# D5035-01.net
KiCad netlist of a schematic drawn in Altium Designer
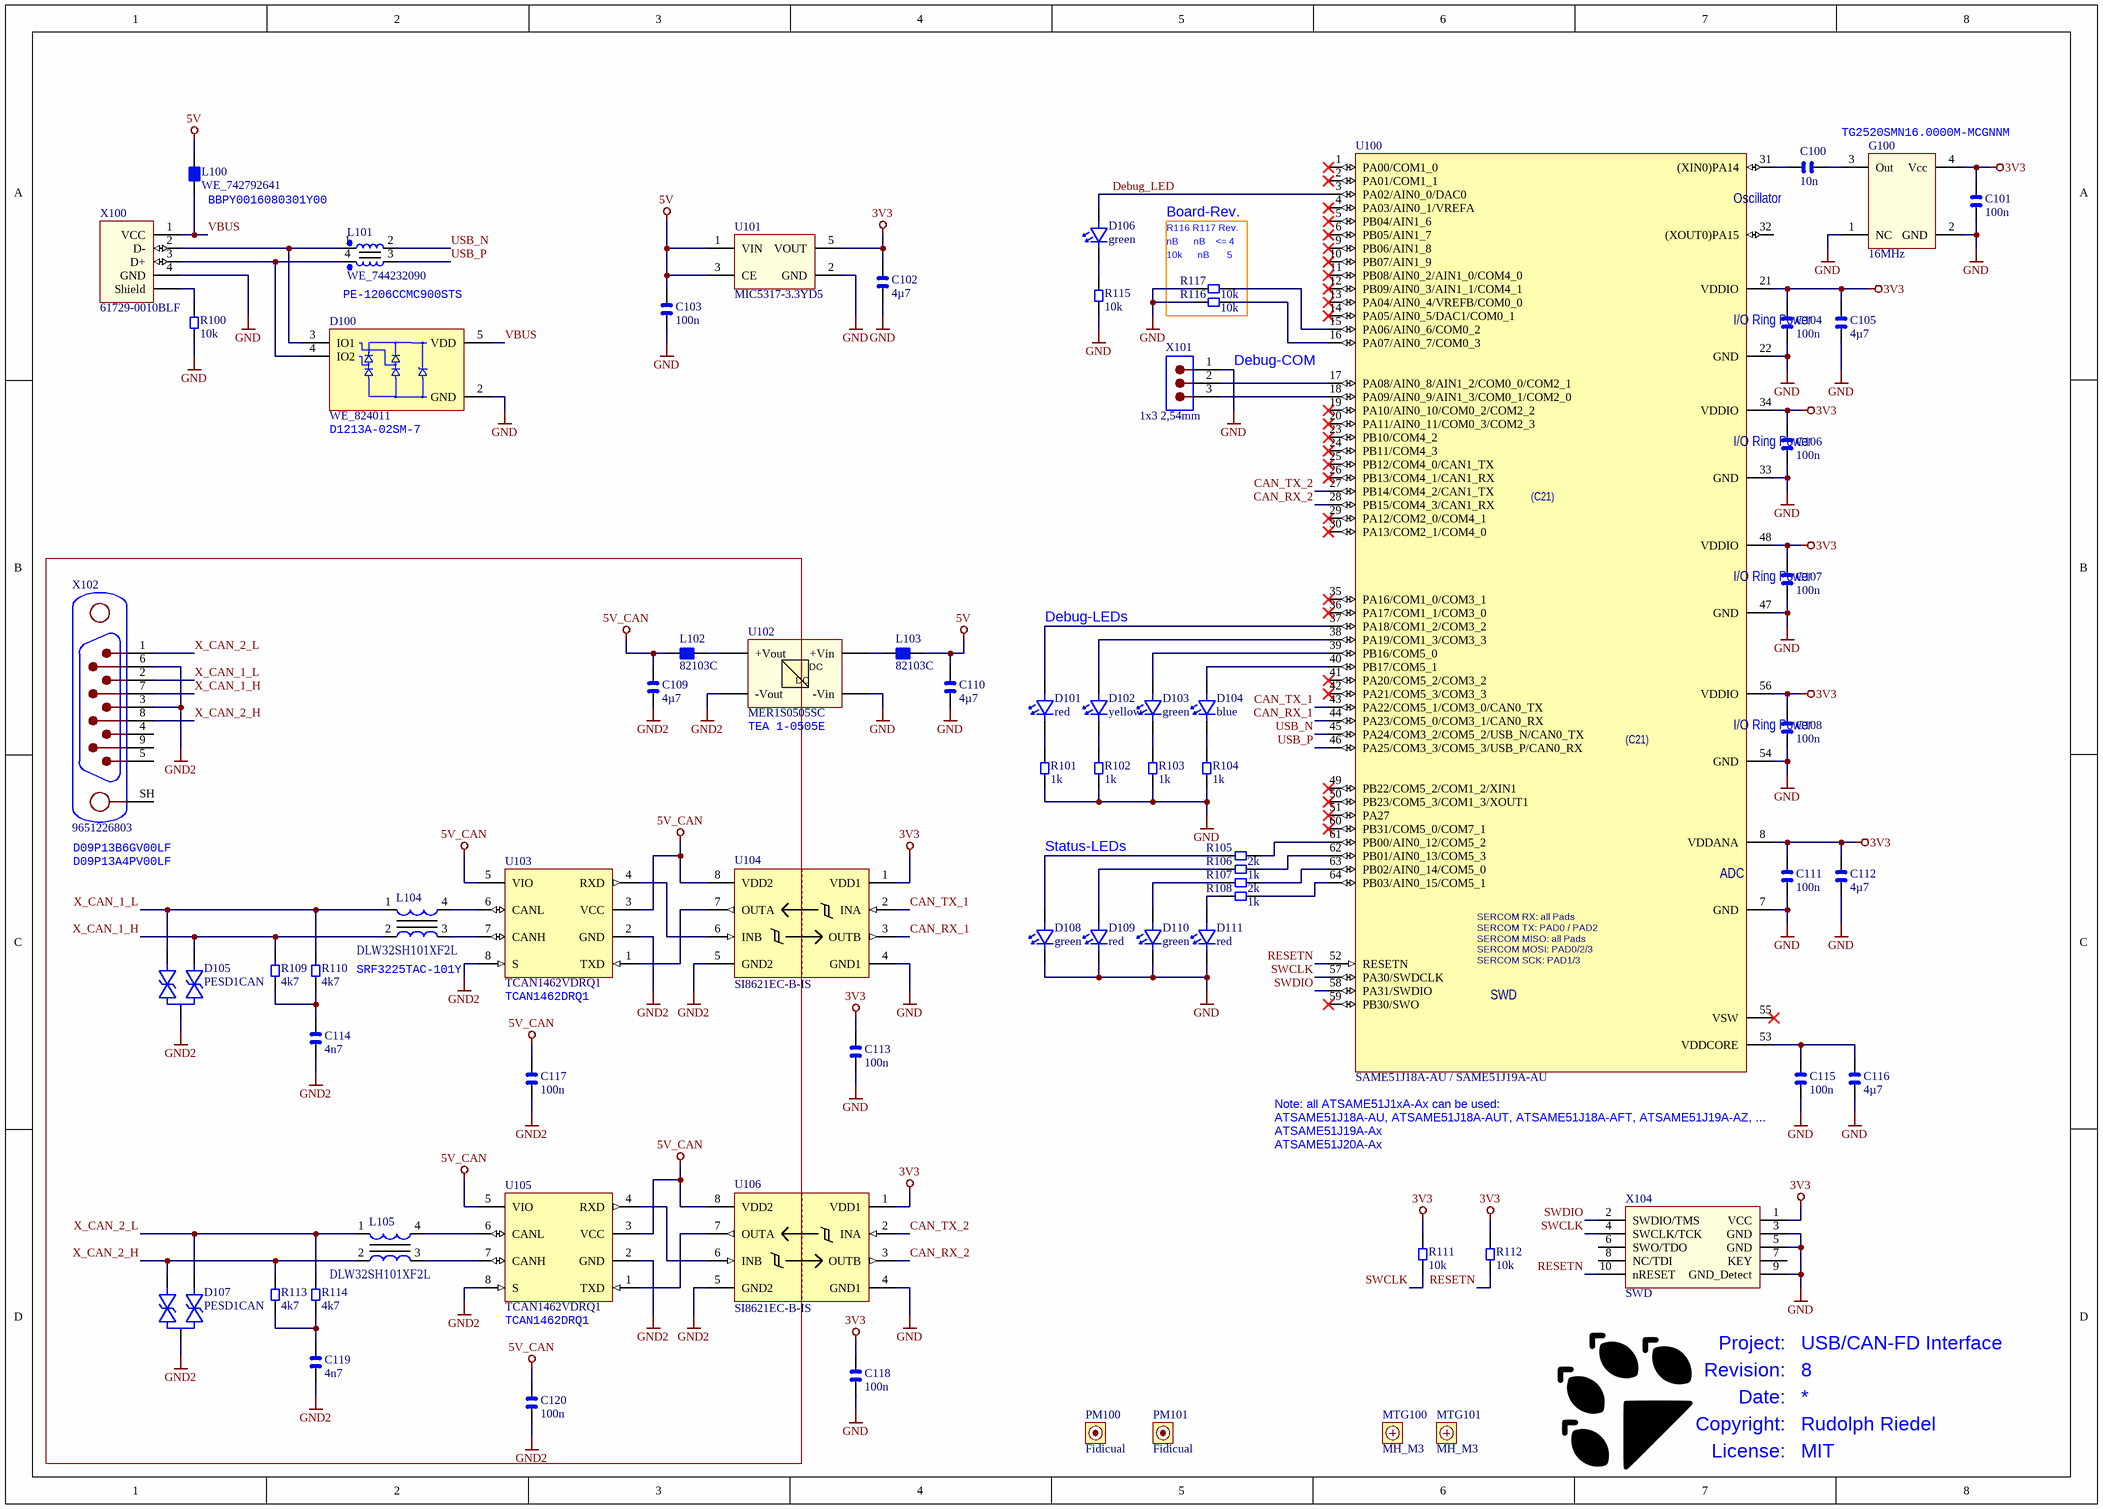
[diagram p0: D5035-01.SchDoc]

(export (version "E")
  (design (tool "Eeschema 10.0.6"))
  (components
    (comp (ref "C100")
      (value "10n")
      (footprint "CAPC1608X09L")
      (description "0603 Chip Capacitor")
      (fields (field (name "PART NUMBER") "CAPC_0603") (field (name "EDITOR") "rriedel"))
      (libsource (lib "HW-Labor_GF") (part "CAP_2_V2"))
    )
    (comp (ref "C101")
      (value "100n")
      (footprint "CAPC1608X09L")
      (description "0603 Chip Capacitor")
      (fields (field (name "PART NUMBER") "CAPC_0603") (field (name "EDITOR") "rriedel"))
      (libsource (lib "HW-Labor_GF") (part "CAP_2_V2"))
    )
    (comp (ref "C102")
      (value "4µ7")
      (footprint "CAPC2012X14L")
      (description "0805 Chip Capacitor")
      (fields (field (name "PART NUMBER") "CAPC_0805") (field (name "EDITOR") "rriedel"))
      (libsource (lib "HW-Labor_GF") (part "CAP_2_V2"))
    )
    (comp (ref "C103")
      (value "100n")
      (footprint "CAPC1608X09L")
      (description "0603 Chip Capacitor")
      (fields (field (name "PART NUMBER") "CAPC_0603") (field (name "EDITOR") "rriedel"))
      (libsource (lib "HW-Labor_GF") (part "CAP_2_V2"))
    )
    (comp (ref "C104")
      (value "100n")
      (footprint "CAPC1608X09L")
      (description "0603 Chip Capacitor")
      (fields (field (name "PART NUMBER") "CAPC_0603") (field (name "EDITOR") "rriedel"))
      (libsource (lib "HW-Labor_GF") (part "CAP_2_V2"))
    )
    (comp (ref "C105")
      (value "4µ7")
      (footprint "CAPC2012X14L")
      (description "0805 Chip Capacitor")
      (fields (field (name "PART NUMBER") "CAPC_0805") (field (name "EDITOR") "rriedel"))
      (libsource (lib "HW-Labor_GF") (part "CAP_2_V2"))
    )
    (comp (ref "C106")
      (value "100n")
      (footprint "CAPC1608X09L")
      (description "0603 Chip Capacitor")
      (fields (field (name "PART NUMBER") "CAPC_0603") (field (name "EDITOR") "rriedel"))
      (libsource (lib "HW-Labor_GF") (part "CAP_2_V2"))
    )
    (comp (ref "C107")
      (value "100n")
      (footprint "CAPC1608X09L")
      (description "0603 Chip Capacitor")
      (fields (field (name "PART NUMBER") "CAPC_0603") (field (name "EDITOR") "rriedel"))
      (libsource (lib "HW-Labor_GF") (part "CAP_2_V2"))
    )
    (comp (ref "C108")
      (value "100n")
      (footprint "CAPC1608X09L")
      (description "0603 Chip Capacitor")
      (fields (field (name "PART NUMBER") "CAPC_0603") (field (name "EDITOR") "rriedel"))
      (libsource (lib "HW-Labor_GF") (part "CAP_2_V2"))
    )
    (comp (ref "C109")
      (value "4µ7")
      (footprint "CAPC2012X14L")
      (description "0805 Chip Capacitor")
      (fields (field (name "PART NUMBER") "CAPC_0805") (field (name "EDITOR") "rriedel"))
      (libsource (lib "HW-Labor_GF") (part "CAP_2_V2"))
    )
    (comp (ref "C110")
      (value "4µ7")
      (footprint "CAPC2012X14L")
      (description "0805 Chip Capacitor")
      (fields (field (name "PART NUMBER") "CAPC_0805") (field (name "EDITOR") "rriedel"))
      (libsource (lib "HW-Labor_GF") (part "CAP_2_V2"))
    )
    (comp (ref "C111")
      (value "100n")
      (footprint "CAPC1608X09L")
      (description "0603 Chip Capacitor")
      (fields (field (name "PART NUMBER") "CAPC_0603") (field (name "EDITOR") "rriedel"))
      (libsource (lib "HW-Labor_GF") (part "CAP_2_V2"))
    )
    (comp (ref "C112")
      (value "4µ7")
      (footprint "CAPC2012X14L")
      (description "0805 Chip Capacitor")
      (fields (field (name "PART NUMBER") "CAPC_0805") (field (name "EDITOR") "rriedel"))
      (libsource (lib "HW-Labor_GF") (part "CAP_2_V2"))
    )
    (comp (ref "C113")
      (value "100n")
      (footprint "CAPC1608X09L")
      (description "0603 Chip Capacitor")
      (fields (field (name "PART NUMBER") "CAPC_0603") (field (name "EDITOR") "rriedel"))
      (libsource (lib "HW-Labor_GF") (part "CAP_2_V2"))
    )
    (comp (ref "C114")
      (value "4n7")
      (footprint "CAPC2012X14L")
      (description "0805 Chip Capacitor")
      (fields (field (name "PART NUMBER") "CAPC_0805") (field (name "EDITOR") "rriedel"))
      (libsource (lib "HW-Labor_GF") (part "CAP_2_V2"))
    )
    (comp (ref "C115")
      (value "100n")
      (footprint "CAPC1608X09L")
      (description "0603 Chip Capacitor")
      (fields (field (name "PART NUMBER") "CAPC_0603") (field (name "EDITOR") "rriedel"))
      (libsource (lib "HW-Labor_GF") (part "CAP_2_V2"))
    )
    (comp (ref "C116")
      (value "4µ7")
      (footprint "CAPC2012X14L")
      (description "0805 Chip Capacitor")
      (fields (field (name "PART NUMBER") "CAPC_0805") (field (name "EDITOR") "rriedel"))
      (libsource (lib "HW-Labor_GF") (part "CAP_2_V2"))
    )
    (comp (ref "C117")
      (value "100n")
      (footprint "CAPC1608X09L")
      (description "0603 Chip Capacitor")
      (fields (field (name "PART NUMBER") "CAPC_0603") (field (name "EDITOR") "rriedel"))
      (libsource (lib "HW-Labor_GF") (part "CAP_2_V2"))
    )
    (comp (ref "C118")
      (value "100n")
      (footprint "CAPC1608X09L")
      (description "0603 Chip Capacitor")
      (fields (field (name "PART NUMBER") "CAPC_0603") (field (name "EDITOR") "rriedel"))
      (libsource (lib "HW-Labor_GF") (part "CAP_2_V2"))
    )
    (comp (ref "C119")
      (value "4n7")
      (footprint "CAPC2012X14L")
      (description "0805 Chip Capacitor")
      (fields (field (name "PART NUMBER") "CAPC_0805") (field (name "EDITOR") "rriedel"))
      (libsource (lib "HW-Labor_GF") (part "CAP_2_V2"))
    )
    (comp (ref "C120")
      (value "100n")
      (footprint "CAPC1608X09L")
      (description "0603 Chip Capacitor")
      (fields (field (name "PART NUMBER") "CAPC_0603") (field (name "EDITOR") "rriedel"))
      (libsource (lib "HW-Labor_GF") (part "CAP_2_V2"))
    )
    (comp (ref "D100")
      (value "WE_824011")
      (footprint "SOT95P280X110-5N")
      (description "TVS Diode Array WE-TVS")
      (fields
        (field (name "MANUFACTURER") "Wuerth")
        (field (name "DISTRIBUTOR_1_PART_NUMBER") "732-4465-1-ND")
        (field (name "EDITOR") "rriedel")
      )
      (libsource (lib "HW-Labor_GF") (part "WE-824011"))
    )
    (comp (ref "D101")
      (value "red")
      (footprint "DIOC1608X06N_LED")
      (description "LED, 0603")
      (fields (field (name "PART NUMBER") "LED_0603") (field (name "EDITOR") "rriedel"))
      (libsource (lib "HW-Labor_GF") (part "LED_generic"))
    )
    (comp (ref "D102")
      (value "yellow")
      (footprint "DIOC1608X06N_LED")
      (description "LED, 0603")
      (fields (field (name "PART NUMBER") "LED_0603") (field (name "EDITOR") "rriedel"))
      (libsource (lib "HW-Labor_GF") (part "LED_generic"))
    )
    (comp (ref "D103")
      (value "green")
      (footprint "DIOC1608X06N_LED")
      (description "LED, 0603")
      (fields (field (name "PART NUMBER") "LED_0603") (field (name "EDITOR") "rriedel"))
      (libsource (lib "HW-Labor_GF") (part "LED_generic"))
    )
    (comp (ref "D104")
      (value "blue")
      (footprint "DIOC1608X06N_LED")
      (description "LED, 0603")
      (fields (field (name "PART NUMBER") "LED_0603") (field (name "EDITOR") "rriedel"))
      (libsource (lib "HW-Labor_GF") (part "LED_generic"))
    )
    (comp (ref "D105")
      (value "PESD1CAN")
      (footprint "SOT95P280X110-3N")
      (description "CAN bus ESD protection diode")
      (fields
        (field (name "MANUFACTURER") "Nexperia")
        (field (name "DISTRIBUTOR_1_PART_NUMBER") "1727-3817-1-ND")
        (field (name "EDITOR") "rriedel")
      )
      (libsource (lib "HW-Labor_GF") (part "PESD1CAN"))
    )
    (comp (ref "D106")
      (value "green")
      (footprint "DIOC1608X06N_LED")
      (description "LED, 0603")
      (fields (field (name "PART NUMBER") "LED_0603") (field (name "EDITOR") "rriedel"))
      (libsource (lib "HW-Labor_GF") (part "LED_generic"))
    )
    (comp (ref "D107")
      (value "PESD1CAN")
      (footprint "SOT95P280X110-3N")
      (description "CAN bus ESD protection diode")
      (fields
        (field (name "MANUFACTURER") "Nexperia")
        (field (name "DISTRIBUTOR_1_PART_NUMBER") "1727-3817-1-ND")
        (field (name "EDITOR") "rriedel")
      )
      (libsource (lib "HW-Labor_GF") (part "PESD1CAN"))
    )
    (comp (ref "D108")
      (value "green")
      (footprint "DIOC1608X06N_LED")
      (description "LED, 0603")
      (fields (field (name "PART NUMBER") "LED_0603") (field (name "EDITOR") "rriedel"))
      (libsource (lib "HW-Labor_GF") (part "LED_generic"))
    )
    (comp (ref "D109")
      (value "red")
      (footprint "DIOC1608X06N_LED")
      (description "LED, 0603")
      (fields (field (name "PART NUMBER") "LED_0603") (field (name "EDITOR") "rriedel"))
      (libsource (lib "HW-Labor_GF") (part "LED_generic"))
    )
    (comp (ref "D110")
      (value "green")
      (footprint "DIOC1608X06N_LED")
      (description "LED, 0603")
      (fields (field (name "PART NUMBER") "LED_0603") (field (name "EDITOR") "rriedel"))
      (libsource (lib "HW-Labor_GF") (part "LED_generic"))
    )
    (comp (ref "D111")
      (value "red")
      (footprint "DIOC1608X06N_LED")
      (description "LED, 0603")
      (fields (field (name "PART NUMBER") "LED_0603") (field (name "EDITOR") "rriedel"))
      (libsource (lib "HW-Labor_GF") (part "LED_generic"))
    )
    (comp (ref "G100")
      (value "16MHz")
      (footprint "TG2520")
      (description "16MHz Oscillator, +/- 0.5ppm")
      (fields
        (field (name "PART NUMBER") "TG2520SMN16.0000M-MCGNNM")
        (field (name "MANUFACTURER") "Epson")
        (field (name "EDITOR") "rriedel")
      )
      (libsource (lib "HW-Labor_GF") (part "TG2520"))
    )
    (comp (ref "L100")
      (value "WE_742792641")
      (footprint "INDC1608X06L")
      (description "SMT EMI suppression ferrite bead WE-CBF")
      (fields
        (field (name "MANUFACTURER") "Wuerth")
        (field (name "DISTRIBUTOR_1_PART_NUMBER") "732-1592-1-ND")
        (field (name "EDITOR") "rriedel")
      )
      (libsource (lib "HW-Labor_GF") (part "IND_2_V1"))
    )
    (comp (ref "L101")
      (value "WE_744232090")
      (footprint "WE_744232090")
      (description "SMD common mode noise suppressor WE-CNSW")
      (fields
        (field (name "MANUFACTURER") "Wuerth")
        (field (name "DISTRIBUTOR_1_PART_NUMBER") "732-1469-1-ND")
        (field (name "EDITOR") "rriedel")
      )
      (libsource (lib "HW-Labor_GF") (part "WE_744232090"))
    )
    (comp (ref "L102")
      (value "82103C")
      (footprint "Murata_8200C")
      (description "10µH, 0,5A, 400mR")
      (fields
        (field (name "MANUFACTURER") "Murata")
        (field (name "DISTRIBUTOR_1_PART_NUMBER") "811-2473-1-ND")
        (field (name "EDITOR") "rriedel")
      )
      (libsource (lib "HW-Labor_GF") (part "IND_2_V1"))
    )
    (comp (ref "L103")
      (value "82103C")
      (footprint "Murata_8200C")
      (description "10µH, 0,5A, 400mR")
      (fields
        (field (name "MANUFACTURER") "Murata")
        (field (name "DISTRIBUTOR_1_PART_NUMBER") "811-2473-1-ND")
        (field (name "EDITOR") "rriedel")
      )
      (libsource (lib "HW-Labor_GF") (part "IND_2_V1"))
    )
    (comp (ref "L104")
      (value "DLW32SH101XF2L‎")
      (footprint "ACT1210")
      (description "Common Mode Filter,  -50°C ... +150°C, AEC-Q200")
      (fields
        (field (name "PART NUMBER") "ACT1210-101-2P-TL00")
        (field (name "MANUFACTURER") "TDK")
        (field (name "EDITOR") "rriedel")
      )
      (libsource (lib "HW-Labor_GF") (part "CAN_DROSSEL"))
    )
    (comp (ref "L105")
      (value "DLW32SH101XF2L‎")
      (footprint "ACT1210")
      (description "Common Mode Filter,  -50°C ... +150°C, AEC-Q200")
      (fields
        (field (name "PART NUMBER") "ACT1210-101-2P-TL00")
        (field (name "MANUFACTURER") "TDK")
        (field (name "EDITOR") "rriedel")
      )
      (libsource (lib "HW-Labor_GF") (part "CAN_DROSSEL"))
    )
    (comp (ref "MTG100")
      (value "MH_M3")
      (footprint "HOLE_3_2MM")
      (description "Mounting-Hole for M3 screws")
      (fields (field (name "EDITOR") "rriedel"))
      (libsource (lib "HW-Labor_GF") (part "MTG_V1"))
    )
    (comp (ref "MTG101")
      (value "MH_M3")
      (footprint "HOLE_3_2MM")
      (description "Mounting-Hole for M3 screws")
      (fields (field (name "EDITOR") "rriedel"))
      (libsource (lib "HW-Labor_GF") (part "MTG_V1"))
    )
    (comp (ref "PM100")
      (value "Fidicual")
      (footprint "PM100")
      (fields (field (name "PART NUMBER") "PM100") (field (name "EDITOR") "rriedel"))
      (libsource (lib "HW-Labor_GF") (part "PM100"))
    )
    (comp (ref "PM101")
      (value "Fidicual")
      (footprint "PM100")
      (fields (field (name "PART NUMBER") "PM100") (field (name "EDITOR") "rriedel"))
      (libsource (lib "HW-Labor_GF") (part "PM100"))
    )
    (comp (ref "R100")
      (value "10k")
      (footprint "RESC1608X06L")
      (description "0603 Chip Resistor")
      (fields (field (name "PART NUMBER") "RESC_0603") (field (name "EDITOR") "rriedel"))
      (libsource (lib "HW-Labor_GF") (part "RES_2_V2"))
    )
    (comp (ref "R101")
      (value "1k")
      (footprint "RESC1608X06L")
      (description "0603 Chip Resistor")
      (fields (field (name "PART NUMBER") "RESC_0603") (field (name "EDITOR") "rriedel"))
      (libsource (lib "HW-Labor_GF") (part "RES_2_V2"))
    )
    (comp (ref "R102")
      (value "1k")
      (footprint "RESC1608X06L")
      (description "0603 Chip Resistor")
      (fields (field (name "PART NUMBER") "RESC_0603") (field (name "EDITOR") "rriedel"))
      (libsource (lib "HW-Labor_GF") (part "RES_2_V2"))
    )
    (comp (ref "R103")
      (value "1k")
      (footprint "RESC1608X06L")
      (description "0603 Chip Resistor")
      (fields (field (name "PART NUMBER") "RESC_0603") (field (name "EDITOR") "rriedel"))
      (libsource (lib "HW-Labor_GF") (part "RES_2_V2"))
    )
    (comp (ref "R104")
      (value "1k")
      (footprint "RESC1608X06L")
      (description "0603 Chip Resistor")
      (fields (field (name "PART NUMBER") "RESC_0603") (field (name "EDITOR") "rriedel"))
      (libsource (lib "HW-Labor_GF") (part "RES_2_V2"))
    )
    (comp (ref "R105")
      (value "2k")
      (footprint "RESC1608X06L")
      (description "0603 Chip Resistor")
      (fields (field (name "PART NUMBER") "RESC_0603") (field (name "EDITOR") "rriedel"))
      (libsource (lib "HW-Labor_GF") (part "RES_2_V2"))
    )
    (comp (ref "R106")
      (value "1k")
      (footprint "RESC1608X06L")
      (description "0603 Chip Resistor")
      (fields (field (name "PART NUMBER") "RESC_0603") (field (name "EDITOR") "rriedel"))
      (libsource (lib "HW-Labor_GF") (part "RES_2_V2"))
    )
    (comp (ref "R107")
      (value "2k")
      (footprint "RESC1608X06L")
      (description "0603 Chip Resistor")
      (fields (field (name "PART NUMBER") "RESC_0603") (field (name "EDITOR") "rriedel"))
      (libsource (lib "HW-Labor_GF") (part "RES_2_V2"))
    )
    (comp (ref "R108")
      (value "1k")
      (footprint "RESC1608X06L")
      (description "0603 Chip Resistor")
      (fields (field (name "PART NUMBER") "RESC_0603") (field (name "EDITOR") "rriedel"))
      (libsource (lib "HW-Labor_GF") (part "RES_2_V2"))
    )
    (comp (ref "R109")
      (value "4k7")
      (footprint "RESC2012X06L")
      (description "0805 Chip Resistor")
      (fields (field (name "PART NUMBER") "RESC_0805") (field (name "EDITOR") "rriedel"))
      (libsource (lib "HW-Labor_GF") (part "RES_2_V2"))
    )
    (comp (ref "R110")
      (value "4k7")
      (footprint "RESC2012X06L")
      (description "0805 Chip Resistor")
      (fields (field (name "PART NUMBER") "RESC_0805") (field (name "EDITOR") "rriedel"))
      (libsource (lib "HW-Labor_GF") (part "RES_2_V2"))
    )
    (comp (ref "R111")
      (value "10k")
      (footprint "RESC1608X06L")
      (description "0603 Chip Resistor")
      (fields (field (name "PART NUMBER") "RESC_0603") (field (name "EDITOR") "rriedel"))
      (libsource (lib "HW-Labor_GF") (part "RES_2_V2"))
    )
    (comp (ref "R112")
      (value "10k")
      (footprint "RESC1608X06L")
      (description "0603 Chip Resistor")
      (fields (field (name "PART NUMBER") "RESC_0603") (field (name "EDITOR") "rriedel"))
      (libsource (lib "HW-Labor_GF") (part "RES_2_V2"))
    )
    (comp (ref "R113")
      (value "4k7")
      (footprint "RESC2012X06L")
      (description "0805 Chip Resistor")
      (fields (field (name "PART NUMBER") "RESC_0805") (field (name "EDITOR") "rriedel"))
      (libsource (lib "HW-Labor_GF") (part "RES_2_V2"))
    )
    (comp (ref "R114")
      (value "4k7")
      (footprint "RESC2012X06L")
      (description "0805 Chip Resistor")
      (fields (field (name "PART NUMBER") "RESC_0805") (field (name "EDITOR") "rriedel"))
      (libsource (lib "HW-Labor_GF") (part "RES_2_V2"))
    )
    (comp (ref "R115")
      (value "10k")
      (footprint "RESC1608X06L")
      (description "0603 Chip Resistor")
      (fields (field (name "PART NUMBER") "RESC_0603") (field (name "EDITOR") "rriedel"))
      (libsource (lib "HW-Labor_GF") (part "RES_2_V2"))
    )
    (comp (ref "R116")
      (value "10k")
      (footprint "RESC1608X06L")
      (description "0603 Chip Resistor")
      (fields (field (name "PART NUMBER") "RESC_0603") (field (name "EDITOR") "rriedel"))
      (libsource (lib "HW-Labor_GF") (part "RES_2_V2"))
    )
    (comp (ref "R117")
      (value "10k")
      (footprint "RESC1608X06L")
      (description "0603 Chip Resistor")
      (fields (field (name "PART NUMBER") "RESC_0603") (field (name "EDITOR") "rriedel"))
      (libsource (lib "HW-Labor_GF") (part "RES_2_V2"))
    )
    (comp (ref "U100")
      (value "SAME51J18A-AU / SAME51J19A-AU")
      (footprint "TSQFP50P1200X1200X120-64N")
      (description "32-bit Microcontroller, 120MHz Cortex M4-F, 512k FLASH,  2x CAN-FD, -40…85°C")
      (fields
        (field (name "PART NUMBER") "SAME51J19A-AU")
        (field (name "MANUFACTURER") "Microchip")
        (field (name "EDITOR") "rriedel")
      )
      (libsource (lib "HW-Labor_GF") (part "SAME5xJxxA-AUx"))
    )
    (comp (ref "U101")
      (value "MIC5317-3.3YD5")
      (footprint "SOT95P280X110-5N")
      (description "100 mA LDO,  Vout= 3,3V, -40°C..125°C")
      (fields
        (field (name "PART NUMBER") "MIC5233-3.3")
        (field (name "MANUFACTURER") "Microchip")
        (field (name "EDITOR") "rriedel")
      )
      (libsource (lib "HW-Labor_GF") (part "LDO_SOT23-5"))
    )
    (comp (ref "U102")
      (value "MER1S0505SC")
      (footprint "MER1SxxxxC")
      (description "Isolated 1W Single Output DC-DC Converters 5V/5V 200mA")
      (fields
        (field (name "MANUFACTURER") "Murata")
        (field (name "DISTRIBUTOR_1_PART_NUMBER") "811-2124-5-ND‎")
        (field (name "EDITOR") "rriedel")
      )
      (libsource (lib "HW-Labor_GF") (part "MER1SxxxxC"))
    )
    (comp (ref "U103")
      (value "TCAN1462VDRQ1")
      (footprint "SOIC127P600X175-8N")
      (description "CAN-FD SIC transceiver 8MBit, VIO Pin")
      (fields
        (field (name "MANUFACTURER") "TI")
        (field (name "DISTRIBUTOR_1_PART_NUMBER") "595-TCAN1462VDRQ1")
        (field (name "EDITOR") "rriedel")
      )
      (libsource (lib "HW-Labor_GF") (part "TJA1051T_3"))
    )
    (comp (ref "U104")
      (value "SI8621EC-B-IS")
      (footprint "SOIC127P600X175-8N")
      (description "Dual channel digital isolator, 150Mbit, 3,75kV")
      (fields
        (field (name "MANUFACTURER") "Silicon Labs")
        (field (name "DISTRIBUTOR_1_PART_NUMBER") "336-4776-1-ND")
        (field (name "EDITOR") "rriedel")
      )
      (libsource (lib "HW-Labor_GF") (part "SI8621"))
    )
    (comp (ref "U105")
      (value "TCAN1462VDRQ1")
      (footprint "SOIC127P600X175-8N")
      (description "CAN-FD SIC transceiver 8MBit, VIO Pin")
      (fields
        (field (name "MANUFACTURER") "TI")
        (field (name "DISTRIBUTOR_1_PART_NUMBER") "595-TCAN1462VDRQ1")
        (field (name "EDITOR") "rriedel")
      )
      (libsource (lib "HW-Labor_GF") (part "TJA1051T_3"))
    )
    (comp (ref "U106")
      (value "SI8621EC-B-IS")
      (footprint "SOIC127P600X175-8N")
      (description "Dual channel digital isolator, 150Mbit, 3,75kV")
      (fields
        (field (name "MANUFACTURER") "Silicon Labs")
        (field (name "DISTRIBUTOR_1_PART_NUMBER") "336-4776-1-ND")
        (field (name "EDITOR") "rriedel")
      )
      (libsource (lib "HW-Labor_GF") (part "SI8621"))
    )
    (comp (ref "X100")
      (value "61729-0010BLF")
      (footprint "61729-xxxxxLF")
      (description "USB-B socket, THT")
      (fields
        (field (name "MANUFACTURER") "Amphenol")
        (field (name "DISTRIBUTOR_1_PART_NUMBER") "609-1039-ND")
        (field (name "EDITOR") "rriedel")
      )
      (libsource (lib "HW-Labor_GF") (part "USB"))
    )
    (comp (ref "X101")
      (value "1x3 2,54mm")
      (footprint "PINH_1x03_2_54mm")
      (description "Pin-Header 2,54 mm 3pins")
      (fields (field (name "PART NUMBER") "PINH_1x3_2_54") (field (name "EDITOR") "rriedel"))
      (libsource (lib "HW-Labor_GF") (part "CONM_1x3_V2"))
    )
    (comp (ref "X102")
      (value "9651226803")
      (footprint "09651226803")
      (description "D-Sub, 9 pin, male, right angle")
      (fields
        (field (name "PART NUMBER") "09651226803")
        (field (name "MANUFACTURER") "Harting")
        (field (name "EDITOR") "rriedel")
      )
      (libsource (lib "HW-Labor_GF") (part "D_Sub_9_Male"))
    )
    (comp (ref "X104")
      (value "SWD")
      (footprint "FTSH-105-01-L-DV-K")
      (description "ARM Debug-Header 2x5 1,27 mm")
      (fields (field (name "EDITOR") "rriedel"))
      (libsource (lib "HW-Labor_GF") (part "SWD"))
    )
  )
  (nets
    (net (code "1") (name "/CAN_RX_1") (class "Default")
      (node (ref "U100") (pin "44") (pinfunction "PA23/COM5_0/COM3_1/CAN0_RX_44") (pintype "bidirectional"))
      (node (ref "U104") (pin "3") (pinfunction "OUTB_3") (pintype "output"))
    )
    (net (code "2") (name "/CAN_RX_2") (class "Default")
      (node (ref "U100") (pin "28") (pinfunction "PB15/COM4_3/CAN1_RX_28") (pintype "bidirectional"))
      (node (ref "U106") (pin "3") (pinfunction "OUTB_3") (pintype "output"))
    )
    (net (code "3") (name "/CAN_TX_1") (class "Default")
      (node (ref "U100") (pin "43") (pinfunction "PA22/COM5_1/COM3_0/CAN0_TX_43") (pintype "bidirectional"))
      (node (ref "U104") (pin "2") (pinfunction "INA_2") (pintype "input"))
    )
    (net (code "4") (name "/CAN_TX_2") (class "Default")
      (node (ref "U100") (pin "27") (pinfunction "PB14/COM4_2/CAN1_TX_27") (pintype "bidirectional"))
      (node (ref "U106") (pin "2") (pinfunction "INA_2") (pintype "input"))
    )
    (net (code "5") (name "/Debug_LED") (class "Default")
      (node (ref "D106") (pin "2") (pinfunction "2_2") (pintype "passive"))
      (node (ref "U100") (pin "3") (pinfunction "PA02/AIN0_0/DAC0_3") (pintype "bidirectional"))
    )
    (net (code "6") (name "/RESETN") (class "Default")
      (node (ref "R112") (pin "1") (pinfunction "1_1") (pintype "passive"))
      (node (ref "U100") (pin "52") (pinfunction "RESETN_52") (pintype "input"))
      (node (ref "X104") (pin "10") (pinfunction "nRESET_10") (pintype "passive"))
    )
    (net (code "7") (name "/SWCLK") (class "Default")
      (node (ref "R111") (pin "1") (pinfunction "1_1") (pintype "passive"))
      (node (ref "U100") (pin "57") (pinfunction "PA30/SWDCLK_57") (pintype "bidirectional"))
      (node (ref "X104") (pin "4") (pinfunction "SWCLK/TCK_4") (pintype "passive"))
    )
    (net (code "8") (name "/SWDIO") (class "Default")
      (node (ref "U100") (pin "58") (pinfunction "PA31/SWDIO_58") (pintype "bidirectional"))
      (node (ref "X104") (pin "2") (pinfunction "SWDIO/TMS_2") (pintype "passive"))
    )
    (net (code "9") (name "/USB_N") (class "Default")
      (node (ref "L101") (pin "2") (pinfunction "2_2") (pintype "passive"))
      (node (ref "U100") (pin "45") (pinfunction "PA24/COM3_2/COM5_2/USB_N/CAN0_TX_45") (pintype "bidirectional"))
    )
    (net (code "10") (name "/USB_P") (class "Default")
      (node (ref "L101") (pin "3") (pinfunction "3_3") (pintype "passive"))
      (node (ref "U100") (pin "46") (pinfunction "PA25/COM3_3/COM5_3/USB_P/CAN0_RX_46") (pintype "bidirectional"))
    )
    (net (code "11") (name "/VBUS") (class "Default")
      (node (ref "D100") (pin "5") (pinfunction "VDD_5") (pintype "passive"))
      (node (ref "L100") (pin "1") (pinfunction "1_1") (pintype "passive"))
      (node (ref "X100") (pin "1") (pinfunction "VCC_1") (pintype "power_in"))
    )
    (net (code "12") (name "/X_CAN_1_H") (class "Default")
      (node (ref "D105") (pin "2") (pinfunction "2_2") (pintype "passive"))
      (node (ref "L104") (pin "2") (pintype "passive"))
      (node (ref "R109") (pin "2") (pinfunction "2_2") (pintype "passive"))
      (node (ref "X102") (pin "7") (pinfunction "7_7") (pintype "passive"))
    )
    (net (code "13") (name "/X_CAN_1_L") (class "Default")
      (node (ref "D105") (pin "1") (pinfunction "1_1") (pintype "passive"))
      (node (ref "L104") (pin "1") (pintype "passive"))
      (node (ref "R110") (pin "2") (pinfunction "2_2") (pintype "passive"))
      (node (ref "X102") (pin "2") (pinfunction "2_2") (pintype "passive"))
    )
    (net (code "14") (name "/X_CAN_2_H") (class "Default")
      (node (ref "D107") (pin "1") (pinfunction "1_1") (pintype "passive"))
      (node (ref "L105") (pin "2") (pintype "passive"))
      (node (ref "R113") (pin "2") (pinfunction "2_2") (pintype "passive"))
      (node (ref "X102") (pin "8") (pinfunction "8_8") (pintype "passive"))
    )
    (net (code "15") (name "/X_CAN_2_L") (class "Default")
      (node (ref "D107") (pin "2") (pinfunction "2_2") (pintype "passive"))
      (node (ref "L105") (pin "1") (pintype "passive"))
      (node (ref "R114") (pin "2") (pinfunction "2_2") (pintype "passive"))
      (node (ref "X102") (pin "1") (pinfunction "1_1") (pintype "passive"))
    )
    (net (code "16") (name "3V3") (class "Default")
      (node (ref "C101") (pin "2") (pinfunction "2_2") (pintype "passive"))
      (node (ref "C102") (pin "2") (pinfunction "2_2") (pintype "passive"))
      (node (ref "C104") (pin "2") (pinfunction "2_2") (pintype "passive"))
      (node (ref "C105") (pin "2") (pinfunction "2_2") (pintype "passive"))
      (node (ref "C106") (pin "2") (pinfunction "2_2") (pintype "passive"))
      (node (ref "C107") (pin "2") (pinfunction "2_2") (pintype "passive"))
      (node (ref "C108") (pin "2") (pinfunction "2_2") (pintype "passive"))
      (node (ref "C111") (pin "2") (pinfunction "2_2") (pintype "passive"))
      (node (ref "C112") (pin "2") (pinfunction "2_2") (pintype "passive"))
      (node (ref "C113") (pin "2") (pinfunction "2_2") (pintype "passive"))
      (node (ref "C118") (pin "2") (pinfunction "2_2") (pintype "passive"))
      (node (ref "G100") (pin "4") (pinfunction "Vcc_4") (pintype "passive"))
      (node (ref "R111") (pin "2") (pinfunction "2_2") (pintype "passive"))
      (node (ref "R112") (pin "2") (pinfunction "2_2") (pintype "passive"))
      (node (ref "U100") (pin "21") (pinfunction "VDDIO_21") (pintype "power_in"))
      (node (ref "U100") (pin "34") (pinfunction "VDDIO_34") (pintype "power_in"))
      (node (ref "U100") (pin "48") (pinfunction "VDDIO_48") (pintype "power_in"))
      (node (ref "U100") (pin "56") (pinfunction "VDDIO_56") (pintype "power_in"))
      (node (ref "U100") (pin "8") (pinfunction "VDDANA_8") (pintype "power_in"))
      (node (ref "U101") (pin "5") (pinfunction "VOUT_5") (pintype "passive"))
      (node (ref "U104") (pin "1") (pinfunction "VDD1_1") (pintype "power_in"))
      (node (ref "U106") (pin "1") (pinfunction "VDD1_1") (pintype "power_in"))
      (node (ref "X104") (pin "1") (pinfunction "VCC_1") (pintype "power_in"))
    )
    (net (code "17") (name "5V") (class "Default")
      (node (ref "C103") (pin "2") (pinfunction "2_2") (pintype "passive"))
      (node (ref "C110") (pin "2") (pinfunction "2_2") (pintype "passive"))
      (node (ref "L100") (pin "2") (pinfunction "2_2") (pintype "passive"))
      (node (ref "L103") (pin "1") (pinfunction "1_1") (pintype "passive"))
      (node (ref "U101") (pin "1") (pinfunction "VIN_1") (pintype "passive"))
      (node (ref "U101") (pin "3") (pinfunction "CE_3") (pintype "passive"))
    )
    (net (code "18") (name "5V_CAN") (class "Default")
      (node (ref "C109") (pin "2") (pinfunction "2_2") (pintype "passive"))
      (node (ref "C117") (pin "2") (pinfunction "2_2") (pintype "passive"))
      (node (ref "C120") (pin "2") (pinfunction "2_2") (pintype "passive"))
      (node (ref "L102") (pin "2") (pinfunction "2_2") (pintype "passive"))
      (node (ref "U103") (pin "3") (pinfunction "VCC_3") (pintype "power_in"))
      (node (ref "U103") (pin "5") (pinfunction "VIO_5") (pintype "power_in"))
      (node (ref "U104") (pin "8") (pinfunction "VDD2_8") (pintype "power_in"))
      (node (ref "U105") (pin "3") (pinfunction "VCC_3") (pintype "power_in"))
      (node (ref "U105") (pin "5") (pinfunction "VIO_5") (pintype "power_in"))
      (node (ref "U106") (pin "8") (pinfunction "VDD2_8") (pintype "power_in"))
    )
    (net (code "19") (name "GND") (class "Default")
      (node (ref "C101") (pin "1") (pinfunction "1_1") (pintype "passive"))
      (node (ref "C102") (pin "1") (pinfunction "1_1") (pintype "passive"))
      (node (ref "C103") (pin "1") (pinfunction "1_1") (pintype "passive"))
      (node (ref "C104") (pin "1") (pinfunction "1_1") (pintype "passive"))
      (node (ref "C105") (pin "1") (pinfunction "1_1") (pintype "passive"))
      (node (ref "C106") (pin "1") (pinfunction "1_1") (pintype "passive"))
      (node (ref "C107") (pin "1") (pinfunction "1_1") (pintype "passive"))
      (node (ref "C108") (pin "1") (pinfunction "1_1") (pintype "passive"))
      (node (ref "C110") (pin "1") (pinfunction "1_1") (pintype "passive"))
      (node (ref "C111") (pin "1") (pinfunction "1_1") (pintype "passive"))
      (node (ref "C112") (pin "1") (pinfunction "1_1") (pintype "passive"))
      (node (ref "C113") (pin "1") (pinfunction "1_1") (pintype "passive"))
      (node (ref "C115") (pin "1") (pinfunction "1_1") (pintype "passive"))
      (node (ref "C116") (pin "1") (pinfunction "1_1") (pintype "passive"))
      (node (ref "C118") (pin "1") (pinfunction "1_1") (pintype "passive"))
      (node (ref "D100") (pin "2") (pinfunction "GND_2") (pintype "passive"))
      (node (ref "D108") (pin "1") (pinfunction "1_1") (pintype "passive"))
      (node (ref "D109") (pin "1") (pinfunction "1_1") (pintype "passive"))
      (node (ref "D110") (pin "1") (pinfunction "1_1") (pintype "passive"))
      (node (ref "D111") (pin "1") (pinfunction "1_1") (pintype "passive"))
      (node (ref "G100") (pin "1") (pinfunction "NC_1") (pintype "passive"))
      (node (ref "G100") (pin "2") (pinfunction "GND_2") (pintype "power_in"))
      (node (ref "R100") (pin "1") (pinfunction "1_1") (pintype "passive"))
      (node (ref "R101") (pin "1") (pinfunction "1_1") (pintype "passive"))
      (node (ref "R102") (pin "1") (pinfunction "1_1") (pintype "passive"))
      (node (ref "R103") (pin "1") (pinfunction "1_1") (pintype "passive"))
      (node (ref "R104") (pin "1") (pinfunction "1_1") (pintype "passive"))
      (node (ref "R115") (pin "1") (pinfunction "1_1") (pintype "passive"))
      (node (ref "R116") (pin "2") (pinfunction "2_2") (pintype "passive"))
      (node (ref "R117") (pin "2") (pinfunction "2_2") (pintype "passive"))
      (node (ref "U100") (pin "22") (pinfunction "GND_22") (pintype "power_in"))
      (node (ref "U100") (pin "33") (pinfunction "GND_33") (pintype "power_in"))
      (node (ref "U100") (pin "47") (pinfunction "GND_47") (pintype "power_in"))
      (node (ref "U100") (pin "54") (pinfunction "GND_54") (pintype "power_in"))
      (node (ref "U100") (pin "7") (pinfunction "GND_7") (pintype "power_in"))
      (node (ref "U101") (pin "2") (pinfunction "GND_2") (pintype "passive"))
      (node (ref "U102") (pin "2") (pinfunction "-Vin_2") (pintype "power_in"))
      (node (ref "U104") (pin "4") (pinfunction "GND1_4") (pintype "power_in"))
      (node (ref "U106") (pin "4") (pinfunction "GND1_4") (pintype "power_in"))
      (node (ref "X100") (pin "4") (pinfunction "GND_4") (pintype "power_in"))
      (node (ref "X101") (pin "1") (pinfunction "1_1") (pintype "passive"))
      (node (ref "X104") (pin "3") (pinfunction "GND_3") (pintype "power_in"))
      (node (ref "X104") (pin "5") (pinfunction "GND_5") (pintype "power_in"))
      (node (ref "X104") (pin "9") (pinfunction "GND_Detect_9") (pintype "power_in"))
    )
    (net (code "20") (name "GND2") (class "Default")
      (node (ref "C109") (pin "1") (pinfunction "1_1") (pintype "passive"))
      (node (ref "C114") (pin "1") (pinfunction "1_1") (pintype "passive"))
      (node (ref "C117") (pin "1") (pinfunction "1_1") (pintype "passive"))
      (node (ref "C119") (pin "1") (pinfunction "1_1") (pintype "passive"))
      (node (ref "C120") (pin "1") (pinfunction "1_1") (pintype "passive"))
      (node (ref "D105") (pin "3") (pinfunction "3_3") (pintype "passive"))
      (node (ref "D107") (pin "3") (pinfunction "3_3") (pintype "passive"))
      (node (ref "U102") (pin "4") (pinfunction "-Vout_4") (pintype "power_in"))
      (node (ref "U103") (pin "2") (pinfunction "GND_2") (pintype "power_in"))
      (node (ref "U103") (pin "8") (pinfunction "S_8") (pintype "input"))
      (node (ref "U104") (pin "5") (pinfunction "GND2_5") (pintype "power_in"))
      (node (ref "U105") (pin "2") (pinfunction "GND_2") (pintype "power_in"))
      (node (ref "U105") (pin "8") (pinfunction "S_8") (pintype "input"))
      (node (ref "U106") (pin "5") (pinfunction "GND2_5") (pintype "power_in"))
      (node (ref "X102") (pin "3") (pinfunction "3_3") (pintype "passive"))
      (node (ref "X102") (pin "6") (pinfunction "6_6") (pintype "passive"))
    )
    (net (code "21") (name "Net-(C114-Pad2)") (class "Default")
      (node (ref "C114") (pin "2") (pinfunction "2_2") (pintype "passive"))
      (node (ref "R109") (pin "1") (pinfunction "1_1") (pintype "passive"))
      (node (ref "R110") (pin "1") (pinfunction "1_1") (pintype "passive"))
    )
    (net (code "22") (name "Net-(C119-Pad2)") (class "Default")
      (node (ref "C119") (pin "2") (pinfunction "2_2") (pintype "passive"))
      (node (ref "R113") (pin "1") (pinfunction "1_1") (pintype "passive"))
      (node (ref "R114") (pin "1") (pinfunction "1_1") (pintype "passive"))
    )
    (net (code "23") (name "Net-(D100-IO1)") (class "Default")
      (node (ref "D100") (pin "3") (pinfunction "IO1_3") (pintype "passive"))
      (node (ref "L101") (pin "1") (pinfunction "1_1") (pintype "passive"))
      (node (ref "X100") (pin "2") (pinfunction "D-_2") (pintype "bidirectional"))
    )
    (net (code "24") (name "Net-(D100-IO2)") (class "Default")
      (node (ref "D100") (pin "4") (pinfunction "IO2_4") (pintype "passive"))
      (node (ref "L101") (pin "4") (pinfunction "4_4") (pintype "passive"))
      (node (ref "X100") (pin "3") (pinfunction "D+_3") (pintype "bidirectional"))
    )
    (net (code "25") (name "Net-(D101-Pad1)") (class "Default")
      (node (ref "D101") (pin "1") (pinfunction "1_1") (pintype "passive"))
      (node (ref "R101") (pin "2") (pinfunction "2_2") (pintype "passive"))
    )
    (net (code "26") (name "Net-(D102-Pad1)") (class "Default")
      (node (ref "D102") (pin "1") (pinfunction "1_1") (pintype "passive"))
      (node (ref "R102") (pin "2") (pinfunction "2_2") (pintype "passive"))
    )
    (net (code "27") (name "Net-(D103-Pad1)") (class "Default")
      (node (ref "D103") (pin "1") (pinfunction "1_1") (pintype "passive"))
      (node (ref "R103") (pin "2") (pinfunction "2_2") (pintype "passive"))
    )
    (net (code "28") (name "Net-(D104-Pad1)") (class "Default")
      (node (ref "D104") (pin "1") (pinfunction "1_1") (pintype "passive"))
      (node (ref "R104") (pin "2") (pinfunction "2_2") (pintype "passive"))
    )
    (net (code "29") (name "Net-(D106-Pad1)") (class "Default")
      (node (ref "D106") (pin "1") (pinfunction "1_1") (pintype "passive"))
      (node (ref "R115") (pin "2") (pinfunction "2_2") (pintype "passive"))
    )
    (net (code "30") (name "Net-(D108-Pad2)") (class "Default")
      (node (ref "D108") (pin "2") (pinfunction "2_2") (pintype "passive"))
      (node (ref "R105") (pin "1") (pinfunction "1_1") (pintype "passive"))
    )
    (net (code "31") (name "Net-(D109-Pad2)") (class "Default")
      (node (ref "D109") (pin "2") (pinfunction "2_2") (pintype "passive"))
      (node (ref "R106") (pin "1") (pinfunction "1_1") (pintype "passive"))
    )
    (net (code "32") (name "Net-(D110-Pad2)") (class "Default")
      (node (ref "D110") (pin "2") (pinfunction "2_2") (pintype "passive"))
      (node (ref "R107") (pin "1") (pinfunction "1_1") (pintype "passive"))
    )
    (net (code "33") (name "Net-(D111-Pad2)") (class "Default")
      (node (ref "D111") (pin "2") (pinfunction "2_2") (pintype "passive"))
      (node (ref "R108") (pin "1") (pinfunction "1_1") (pintype "passive"))
    )
    (net (code "34") (name "Net-(G100-Out)") (class "Default")
      (node (ref "C100") (pin "2") (pinfunction "2_2") (pintype "passive"))
      (node (ref "G100") (pin "3") (pinfunction "Out_3") (pintype "passive"))
    )
    (net (code "35") (name "Net-(U100-(XIN0)PA14)") (class "Default")
      (node (ref "C100") (pin "1") (pinfunction "1_1") (pintype "passive"))
      (node (ref "U100") (pin "31") (pinfunction "(XIN0)PA14_31") (pintype "bidirectional"))
    )
    (net (code "36") (name "Net-(U100-PA06{slash}AIN0_6{slash}COM0_2)") (class "Default")
      (node (ref "R117") (pin "1") (pinfunction "1_1") (pintype "passive"))
      (node (ref "U100") (pin "15") (pinfunction "PA06/AIN0_6/COM0_2_15") (pintype "bidirectional"))
    )
    (net (code "37") (name "Net-(U100-PA07{slash}AIN0_7{slash}COM0_3)") (class "Default")
      (node (ref "R116") (pin "1") (pinfunction "1_1") (pintype "passive"))
      (node (ref "U100") (pin "16") (pinfunction "PA07/AIN0_7/COM0_3_16") (pintype "bidirectional"))
    )
    (net (code "38") (name "Net-(U100-PA08{slash}AIN0_8{slash}AIN1_2{slash}COM0_0{slash}COM2_1)") (class "Default")
      (node (ref "U100") (pin "17") (pinfunction "PA08/AIN0_8/AIN1_2/COM0_0/COM2_1_17") (pintype "bidirectional"))
      (node (ref "X101") (pin "2") (pinfunction "2_2") (pintype "passive"))
    )
    (net (code "39") (name "Net-(U100-PA09{slash}AIN0_9{slash}AIN1_3{slash}COM0_1{slash}COM2_0)") (class "Default")
      (node (ref "U100") (pin "18") (pinfunction "PA09/AIN0_9/AIN1_3/COM0_1/COM2_0_18") (pintype "bidirectional"))
      (node (ref "X101") (pin "3") (pinfunction "3_3") (pintype "passive"))
    )
    (net (code "40") (name "Net-(U100-PA18{slash}COM1_2{slash}COM3_2)") (class "Default")
      (node (ref "D101") (pin "2") (pinfunction "2_2") (pintype "passive"))
      (node (ref "U100") (pin "37") (pinfunction "PA18/COM1_2/COM3_2_37") (pintype "bidirectional"))
    )
    (net (code "41") (name "Net-(U100-PA19{slash}COM1_3{slash}COM3_3)") (class "Default")
      (node (ref "D102") (pin "2") (pinfunction "2_2") (pintype "passive"))
      (node (ref "U100") (pin "38") (pinfunction "PA19/COM1_3/COM3_3_38") (pintype "bidirectional"))
    )
    (net (code "42") (name "Net-(U100-PB00{slash}AIN0_12{slash}COM5_2)") (class "Default")
      (node (ref "R105") (pin "2") (pinfunction "2_2") (pintype "passive"))
      (node (ref "U100") (pin "61") (pinfunction "PB00/AIN0_12/COM5_2_61") (pintype "bidirectional"))
    )
    (net (code "43") (name "Net-(U100-PB01{slash}AIN0_13{slash}COM5_3)") (class "Default")
      (node (ref "R106") (pin "2") (pinfunction "2_2") (pintype "passive"))
      (node (ref "U100") (pin "62") (pinfunction "PB01/AIN0_13/COM5_3_62") (pintype "bidirectional"))
    )
    (net (code "44") (name "Net-(U100-PB02{slash}AIN0_14{slash}COM5_0)") (class "Default")
      (node (ref "R107") (pin "2") (pinfunction "2_2") (pintype "passive"))
      (node (ref "U100") (pin "63") (pinfunction "PB02/AIN0_14/COM5_0_63") (pintype "bidirectional"))
    )
    (net (code "45") (name "Net-(U100-PB03{slash}AIN0_15{slash}COM5_1)") (class "Default")
      (node (ref "R108") (pin "2") (pinfunction "2_2") (pintype "passive"))
      (node (ref "U100") (pin "64") (pinfunction "PB03/AIN0_15/COM5_1_64") (pintype "bidirectional"))
    )
    (net (code "46") (name "Net-(U100-PB16{slash}COM5_0)") (class "Default")
      (node (ref "D103") (pin "2") (pinfunction "2_2") (pintype "passive"))
      (node (ref "U100") (pin "39") (pinfunction "PB16/COM5_0_39") (pintype "bidirectional"))
    )
    (net (code "47") (name "Net-(U100-PB17{slash}COM5_1)") (class "Default")
      (node (ref "D104") (pin "2") (pinfunction "2_2") (pintype "passive"))
      (node (ref "U100") (pin "40") (pinfunction "PB17/COM5_1_40") (pintype "bidirectional"))
    )
    (net (code "48") (name "Net-(U100-VDDCORE)") (class "Default")
      (node (ref "C115") (pin "2") (pinfunction "2_2") (pintype "passive"))
      (node (ref "C116") (pin "2") (pinfunction "2_2") (pintype "passive"))
      (node (ref "U100") (pin "53") (pinfunction "VDDCORE_53") (pintype "passive"))
    )
    (net (code "49") (name "Net-(U102-+Vin)") (class "Default")
      (node (ref "L103") (pin "2") (pinfunction "2_2") (pintype "passive"))
      (node (ref "U102") (pin "1") (pinfunction "+Vin_1") (pintype "power_in"))
    )
    (net (code "50") (name "Net-(U102-+Vout)") (class "Default")
      (node (ref "L102") (pin "1") (pinfunction "1_1") (pintype "passive"))
      (node (ref "U102") (pin "6") (pinfunction "+Vout_6") (pintype "power_in"))
    )
    (net (code "51") (name "Net-(U103-CANH)") (class "Default")
      (node (ref "L104") (pin "3") (pintype "passive"))
      (node (ref "U103") (pin "7") (pinfunction "CANH_7") (pintype "bidirectional"))
    )
    (net (code "52") (name "Net-(U103-CANL)") (class "Default")
      (node (ref "L104") (pin "4") (pintype "passive"))
      (node (ref "U103") (pin "6") (pinfunction "CANL_6") (pintype "bidirectional"))
    )
    (net (code "53") (name "Net-(U103-RXD)") (class "Default")
      (node (ref "U103") (pin "4") (pinfunction "RXD_4") (pintype "output"))
      (node (ref "U104") (pin "6") (pinfunction "INB_6") (pintype "input"))
    )
    (net (code "54") (name "Net-(U103-TXD)") (class "Default")
      (node (ref "U103") (pin "1") (pinfunction "TXD_1") (pintype "input"))
      (node (ref "U104") (pin "7") (pinfunction "OUTA_7") (pintype "output"))
    )
    (net (code "55") (name "Net-(U105-CANH)") (class "Default")
      (node (ref "L105") (pin "3") (pintype "passive"))
      (node (ref "U105") (pin "7") (pinfunction "CANH_7") (pintype "bidirectional"))
    )
    (net (code "56") (name "Net-(U105-CANL)") (class "Default")
      (node (ref "L105") (pin "4") (pintype "passive"))
      (node (ref "U105") (pin "6") (pinfunction "CANL_6") (pintype "bidirectional"))
    )
    (net (code "57") (name "Net-(U105-RXD)") (class "Default")
      (node (ref "U105") (pin "4") (pinfunction "RXD_4") (pintype "output"))
      (node (ref "U106") (pin "6") (pinfunction "INB_6") (pintype "input"))
    )
    (net (code "58") (name "Net-(U105-TXD)") (class "Default")
      (node (ref "U105") (pin "1") (pinfunction "TXD_1") (pintype "input"))
      (node (ref "U106") (pin "7") (pinfunction "OUTA_7") (pintype "output"))
    )
    (net (code "59") (name "Net-(X100-Shield)") (class "Default")
      (node (ref "R100") (pin "2") (pinfunction "2_2") (pintype "passive"))
      (node (ref "X100") (pin "Shell") (pinfunction "Shield_Shell") (pintype "passive"))
    )
    (net (code "60") (name "unconnected-(U100-(XOUT0)PA15-Pad32)") (class "Default")
      (node (ref "U100") (pin "32") (pinfunction "(XOUT0)PA15_32") (pintype "bidirectional"))
    )
    (net (code "61") (name "unconnected-(U100-PA00{slash}COM1_0-Pad1)") (class "Default")
      (node (ref "U100") (pin "1") (pinfunction "PA00/COM1_0_1") (pintype "bidirectional+no_connect"))
    )
    (net (code "62") (name "unconnected-(U100-PA01{slash}COM1_1-Pad2)") (class "Default")
      (node (ref "U100") (pin "2") (pinfunction "PA01/COM1_1_2") (pintype "bidirectional+no_connect"))
    )
    (net (code "63") (name "unconnected-(U100-PA03{slash}AIN0_1{slash}VREFA-Pad4)") (class "Default")
      (node (ref "U100") (pin "4") (pinfunction "PA03/AIN0_1/VREFA_4") (pintype "bidirectional+no_connect"))
    )
    (net (code "64") (name "unconnected-(U100-PA04{slash}AIN0_4{slash}VREFB{slash}COM0_0-Pad13)") (class "Default")
      (node (ref "U100") (pin "13") (pinfunction "PA04/AIN0_4/VREFB/COM0_0_13") (pintype "bidirectional+no_connect"))
    )
    (net (code "65") (name "unconnected-(U100-PA05{slash}AIN0_5{slash}DAC1{slash}COM0_1-Pad14)") (class "Default")
      (node (ref "U100") (pin "14") (pinfunction "PA05/AIN0_5/DAC1/COM0_1_14") (pintype "bidirectional+no_connect"))
    )
    (net (code "66") (name "unconnected-(U100-PA10{slash}AIN0_10{slash}COM0_2{slash}COM2_2-Pad19)") (class "Default")
      (node (ref "U100") (pin "19") (pinfunction "PA10/AIN0_10/COM0_2/COM2_2_19") (pintype "bidirectional+no_connect"))
    )
    (net (code "67") (name "unconnected-(U100-PA11{slash}AIN0_11{slash}COM0_3{slash}COM2_3-Pad20)") (class "Default")
      (node (ref "U100") (pin "20") (pinfunction "PA11/AIN0_11/COM0_3/COM2_3_20") (pintype "bidirectional+no_connect"))
    )
    (net (code "68") (name "unconnected-(U100-PA12{slash}COM2_0{slash}COM4_1-Pad29)") (class "Default")
      (node (ref "U100") (pin "29") (pinfunction "PA12/COM2_0/COM4_1_29") (pintype "bidirectional+no_connect"))
    )
    (net (code "69") (name "unconnected-(U100-PA13{slash}COM2_1{slash}COM4_0-Pad30)") (class "Default")
      (node (ref "U100") (pin "30") (pinfunction "PA13/COM2_1/COM4_0_30") (pintype "bidirectional+no_connect"))
    )
    (net (code "70") (name "unconnected-(U100-PA16{slash}COM1_0{slash}COM3_1-Pad35)") (class "Default")
      (node (ref "U100") (pin "35") (pinfunction "PA16/COM1_0/COM3_1_35") (pintype "bidirectional+no_connect"))
    )
    (net (code "71") (name "unconnected-(U100-PA17{slash}COM1_1{slash}COM3_0-Pad36)") (class "Default")
      (node (ref "U100") (pin "36") (pinfunction "PA17/COM1_1/COM3_0_36") (pintype "bidirectional+no_connect"))
    )
    (net (code "72") (name "unconnected-(U100-PA20{slash}COM5_2{slash}COM3_2-Pad41)") (class "Default")
      (node (ref "U100") (pin "41") (pinfunction "PA20/COM5_2/COM3_2_41") (pintype "bidirectional+no_connect"))
    )
    (net (code "73") (name "unconnected-(U100-PA21{slash}COM5_3{slash}COM3_3-Pad42)") (class "Default")
      (node (ref "U100") (pin "42") (pinfunction "PA21/COM5_3/COM3_3_42") (pintype "bidirectional+no_connect"))
    )
    (net (code "74") (name "unconnected-(U100-PA27-Pad51)") (class "Default")
      (node (ref "U100") (pin "51") (pinfunction "PA27_51") (pintype "bidirectional+no_connect"))
    )
    (net (code "75") (name "unconnected-(U100-PB04{slash}AIN1_6-Pad5)") (class "Default")
      (node (ref "U100") (pin "5") (pinfunction "PB04/AIN1_6_5") (pintype "bidirectional+no_connect"))
    )
    (net (code "76") (name "unconnected-(U100-PB05{slash}AIN1_7-Pad6)") (class "Default")
      (node (ref "U100") (pin "6") (pinfunction "PB05/AIN1_7_6") (pintype "bidirectional+no_connect"))
    )
    (net (code "77") (name "unconnected-(U100-PB06{slash}AIN1_8-Pad9)") (class "Default")
      (node (ref "U100") (pin "9") (pinfunction "PB06/AIN1_8_9") (pintype "bidirectional+no_connect"))
    )
    (net (code "78") (name "unconnected-(U100-PB07{slash}AIN1_9-Pad10)") (class "Default")
      (node (ref "U100") (pin "10") (pinfunction "PB07/AIN1_9_10") (pintype "bidirectional+no_connect"))
    )
    (net (code "79") (name "unconnected-(U100-PB08{slash}AIN0_2{slash}AIN1_0{slash}COM4_0-Pad11)") (class "Default")
      (node (ref "U100") (pin "11") (pinfunction "PB08/AIN0_2/AIN1_0/COM4_0_11") (pintype "bidirectional+no_connect"))
    )
    (net (code "80") (name "unconnected-(U100-PB09{slash}AIN0_3{slash}AIN1_1{slash}COM4_1-Pad12)") (class "Default")
      (node (ref "U100") (pin "12") (pinfunction "PB09/AIN0_3/AIN1_1/COM4_1_12") (pintype "bidirectional+no_connect"))
    )
    (net (code "81") (name "unconnected-(U100-PB10{slash}COM4_2-Pad23)") (class "Default")
      (node (ref "U100") (pin "23") (pinfunction "PB10/COM4_2_23") (pintype "bidirectional+no_connect"))
    )
    (net (code "82") (name "unconnected-(U100-PB11{slash}COM4_3-Pad24)") (class "Default")
      (node (ref "U100") (pin "24") (pinfunction "PB11/COM4_3_24") (pintype "bidirectional+no_connect"))
    )
    (net (code "83") (name "unconnected-(U100-PB12{slash}COM4_0{slash}CAN1_TX-Pad25)") (class "Default")
      (node (ref "U100") (pin "25") (pinfunction "PB12/COM4_0/CAN1_TX_25") (pintype "bidirectional+no_connect"))
    )
    (net (code "84") (name "unconnected-(U100-PB13{slash}COM4_1{slash}CAN1_RX-Pad26)") (class "Default")
      (node (ref "U100") (pin "26") (pinfunction "PB13/COM4_1/CAN1_RX_26") (pintype "bidirectional+no_connect"))
    )
    (net (code "85") (name "unconnected-(U100-PB22{slash}COM5_2{slash}COM1_2{slash}XIN1-Pad49)") (class "Default")
      (node (ref "U100") (pin "49") (pinfunction "PB22/COM5_2/COM1_2/XIN1_49") (pintype "bidirectional+no_connect"))
    )
    (net (code "86") (name "unconnected-(U100-PB23{slash}COM5_3{slash}COM1_3{slash}XOUT1-Pad50)") (class "Default")
      (node (ref "U100") (pin "50") (pinfunction "PB23/COM5_3/COM1_3/XOUT1_50") (pintype "bidirectional+no_connect"))
    )
    (net (code "87") (name "unconnected-(U100-PB30{slash}SWO-Pad59)") (class "Default")
      (node (ref "U100") (pin "59") (pinfunction "PB30/SWO_59") (pintype "bidirectional+no_connect"))
    )
    (net (code "88") (name "unconnected-(U100-PB31{slash}COM5_0{slash}COM7_1-Pad60)") (class "Default")
      (node (ref "U100") (pin "60") (pinfunction "PB31/COM5_0/COM7_1_60") (pintype "bidirectional+no_connect"))
    )
    (net (code "89") (name "unconnected-(U100-VSW-Pad55)") (class "Default")
      (node (ref "U100") (pin "55") (pinfunction "VSW_55") (pintype "passive+no_connect"))
    )
    (net (code "90") (name "unconnected-(X102-Pad4)") (class "Default")
      (node (ref "X102") (pin "4") (pinfunction "4_4") (pintype "passive"))
    )
    (net (code "91") (name "unconnected-(X102-Pad5)") (class "Default")
      (node (ref "X102") (pin "5") (pinfunction "5_5") (pintype "passive"))
    )
    (net (code "92") (name "unconnected-(X102-Pad9)") (class "Default")
      (node (ref "X102") (pin "9") (pinfunction "9_9") (pintype "passive"))
    )
    (net (code "93") (name "unconnected-(X102-PadSH)") (class "Default")
      (node (ref "X102") (pin "SH") (pinfunction "SH_SH") (pintype "passive"))
    )
    (net (code "94") (name "unconnected-(X104-KEY-Pad7)") (class "Default")
      (node (ref "X104") (pin "7") (pinfunction "KEY_7") (pintype "passive"))
    )
    (net (code "95") (name "unconnected-(X104-NC{slash}TDI-Pad8)") (class "Default")
      (node (ref "X104") (pin "8") (pinfunction "NC/TDI_8") (pintype "passive"))
    )
    (net (code "96") (name "unconnected-(X104-SWO{slash}TDO-Pad6)") (class "Default")
      (node (ref "X104") (pin "6") (pinfunction "SWO/TDO_6") (pintype "passive"))
    )
  )
)
